# wigler_ariel.net
KiCad netlist of a schematic drawn in EasyEDA
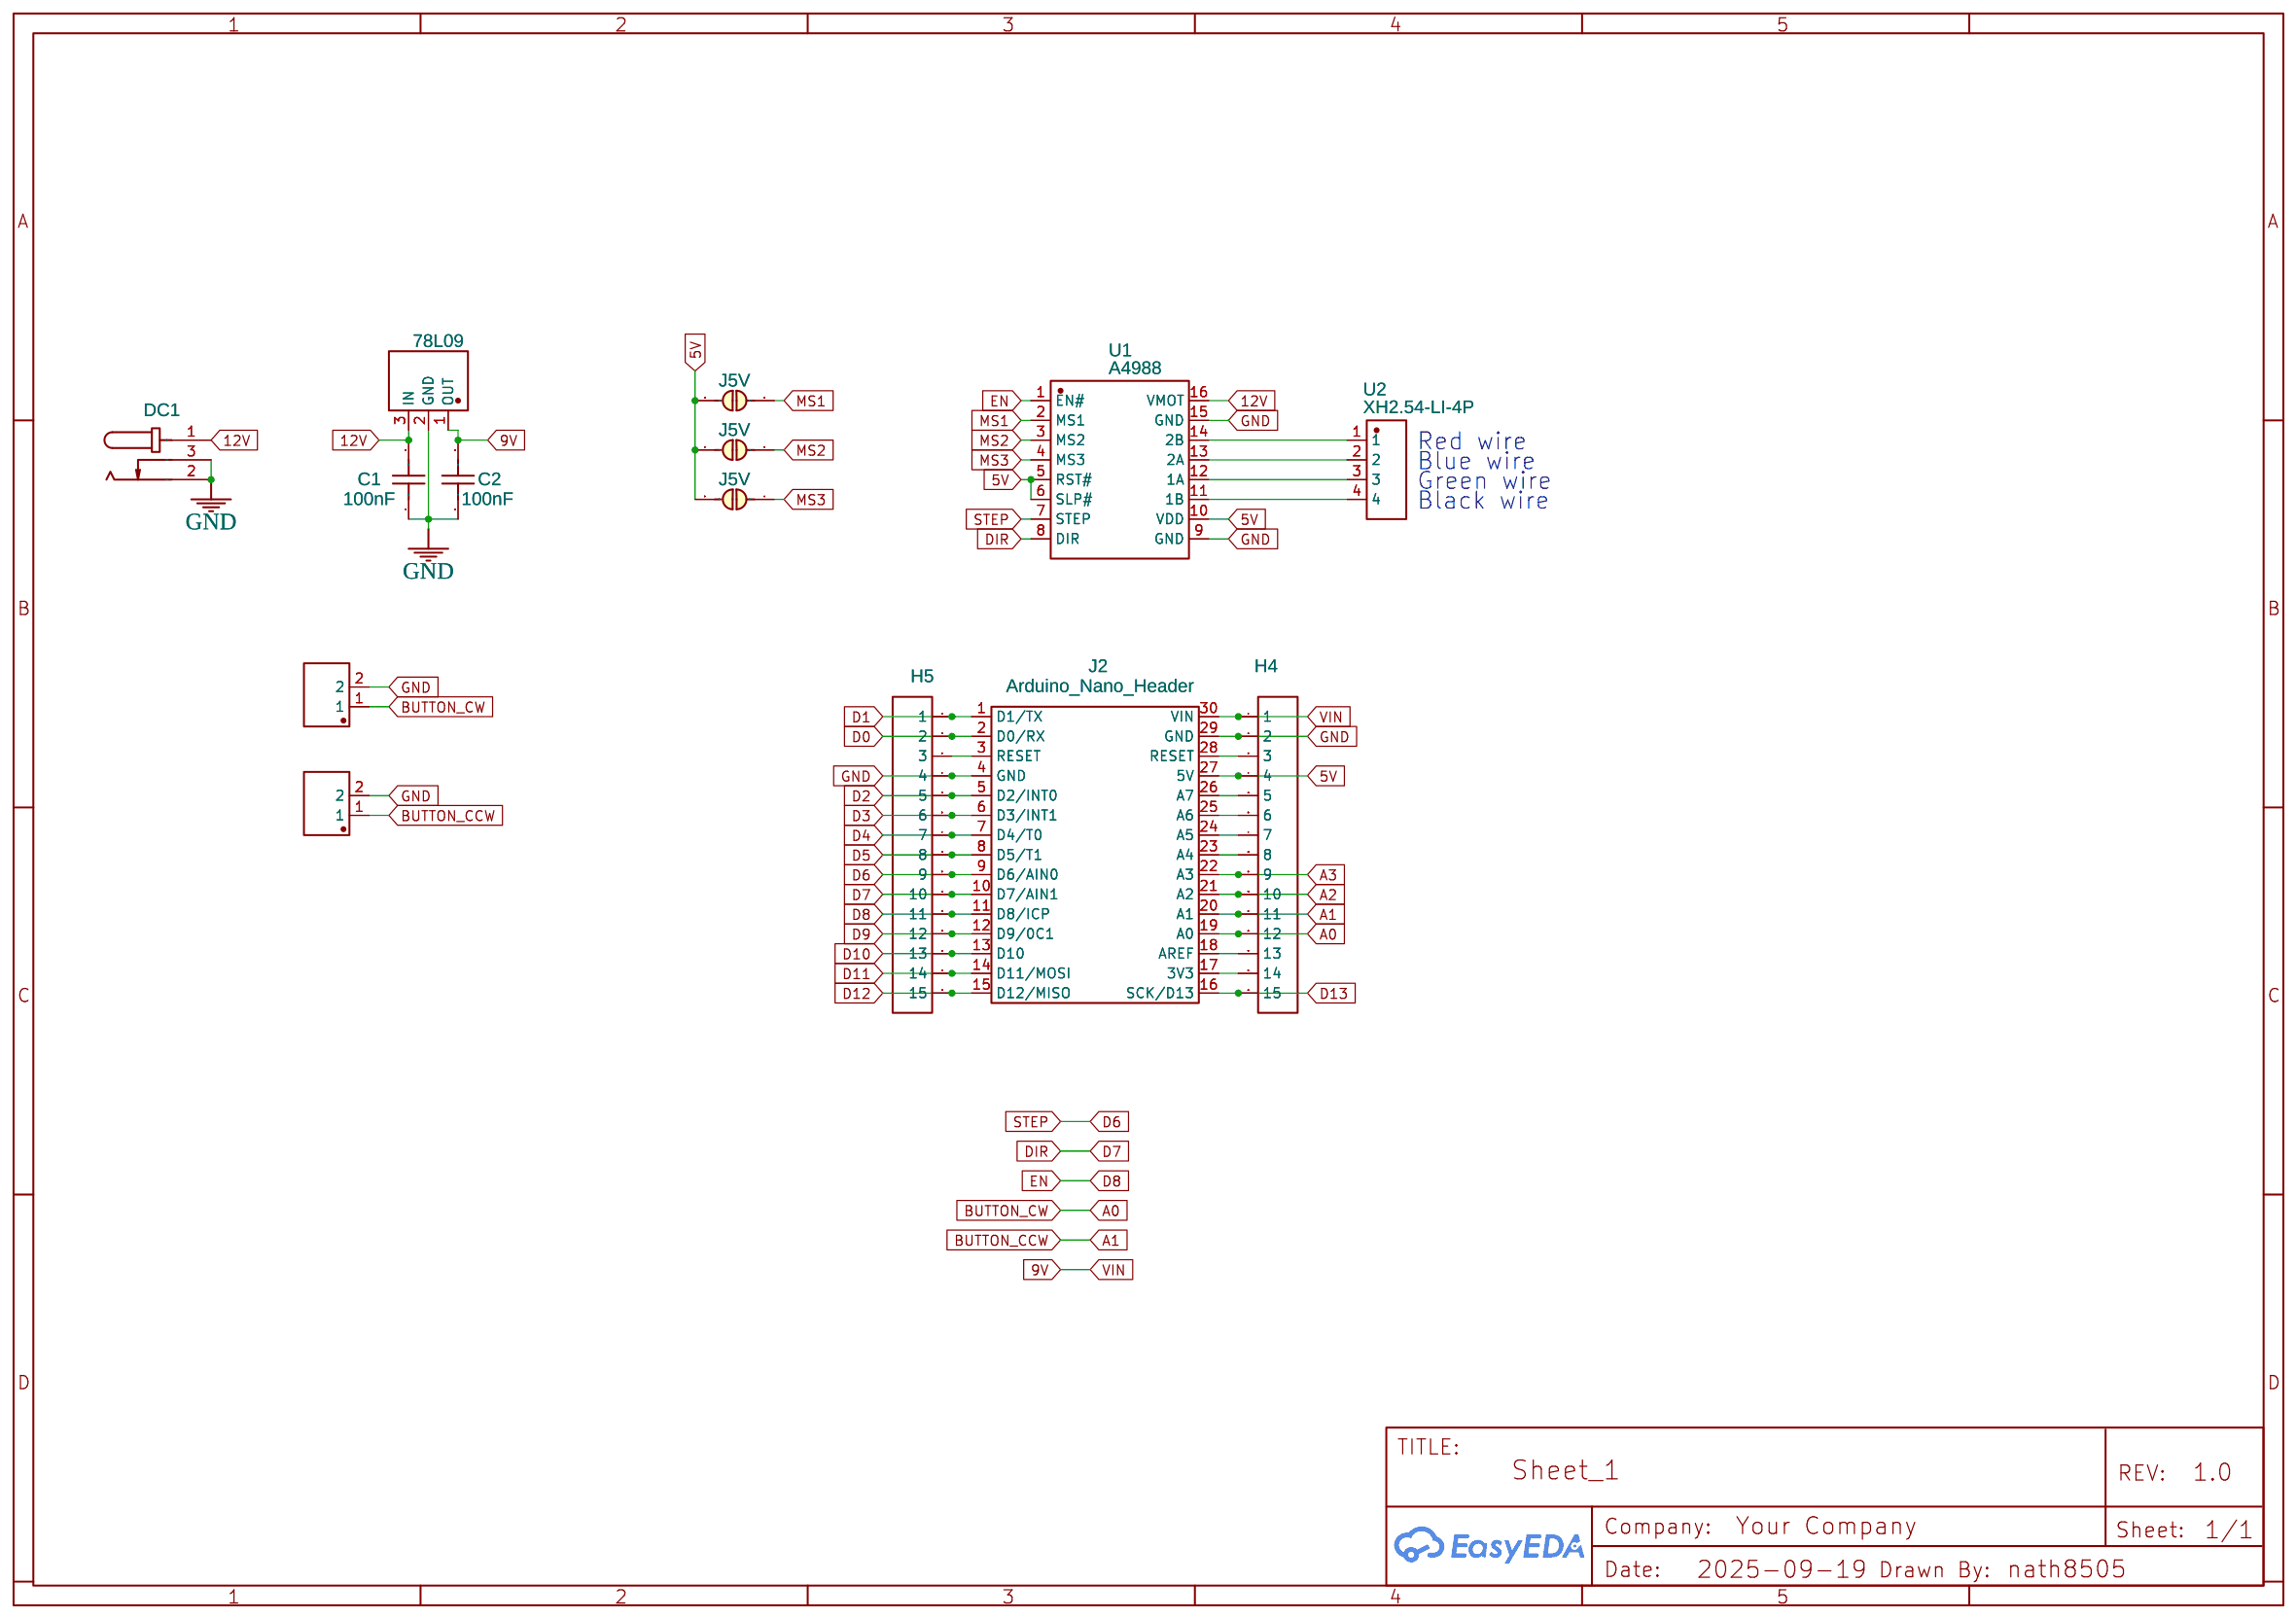
[diagram p0: schematic sheet]

(export (version "E")
  (design (tool "Eeschema 10.0.6"))
  (components
    (comp (ref "C1")
      (value "100nF")
      (fields
        (field (name "Manufacturer Part") "CC0603KRX7R9BB104")
        (field (name "Manufacturer") "YAGEO(国巨)")
      )
      (libsource (lib "") (part "CC0603KRX7R9BB104"))
    )
    (comp (ref "C2")
      (value "100nF")
      (fields
        (field (name "Manufacturer Part") "CC0603KRX7R9BB104")
        (field (name "Manufacturer") "YAGEO(国巨)")
      )
      (libsource (lib "") (part "CC0603KRX7R9BB104"))
    )
    (comp (ref "D7")
      (value "B+")
      (fields (field (name "Manufacturer Part") "KF2510-2A") (field (name "Manufacturer") "BOOMELE"))
      (libsource (lib "") (part "KF2510-2A"))
    )
    (comp (ref "D8")
      (value "B-")
      (fields (field (name "Manufacturer Part") "KF2510-2A") (field (name "Manufacturer") "BOOMELE"))
      (libsource (lib "") (part "KF2510-2A"))
    )
    (comp (ref "DC1")
      (value "DC")
      (fields (field (name "Manufacturer Part") "DC005-2.0MM") (field (name "Manufacturer") "SOFNG"))
      (libsource (lib "") (part "DC005-2.0MM"))
    )
    (comp (ref "H4") (value "HDR-F-2.54_1x15") (libsource (lib "") (part "HDR-F-2.54_1x15")))
    (comp (ref "H5") (value "HDR-F-2.54_1x15") (libsource (lib "") (part "HDR-F-2.54_1x15_1")))
    (comp (ref "J2") (value "Arduino_Nano_Header") (libsource (lib "") (part "Arduino_Nano_Header")))
    (comp (ref "J9V_1") (value "J5V") (libsource (lib "") (part "JUMPER-SMT_2")))
    (comp (ref "J9V_2") (value "J5V") (libsource (lib "") (part "JUMPER-SMT_2")))
    (comp (ref "J9V_3") (value "J5V") (libsource (lib "") (part "JUMPER-SMT_2")))
    (comp (ref "U1") (value "A4988") (libsource (lib "") (part "A4988")))
    (comp (ref "U2") (value "XH2.54-LI-4P") (libsource (lib "") (part "XH2.54-LI-4P")))
    (comp (ref "U3")
      (value "78L09")
      (fields (field (name "Manufacturer") "CBI(创基)"))
      (libsource (lib "") (part "78L09U 78L09"))
    )
  )
  (nets
    (net (code "1") (name "5V") (class "Default")
      (node (ref "H4") (pin "4") (pinfunction "4_4") (pintype "unspecified"))
      (node (ref "J2") (pin "27") (pinfunction "5V_27") (pintype "unspecified"))
      (node (ref "J9V_1") (pin "2") (pinfunction "2_2") (pintype "bidirectional"))
      (node (ref "J9V_2") (pin "2") (pinfunction "2_2") (pintype "bidirectional"))
      (node (ref "J9V_3") (pin "2") (pinfunction "2_2") (pintype "bidirectional"))
      (node (ref "U1") (pin "10") (pinfunction "VDD_10") (pintype "unspecified"))
      (node (ref "U1") (pin "5") (pinfunction "RST#_5") (pintype "unspecified"))
      (node (ref "U1") (pin "6") (pinfunction "SLP#_6") (pintype "unspecified"))
    )
    (net (code "2") (name "9V") (class "Default")
      (node (ref "C2") (pin "2") (pinfunction "2_2") (pintype "unspecified"))
      (node (ref "H4") (pin "1") (pinfunction "1_1") (pintype "unspecified"))
      (node (ref "J2") (pin "30") (pinfunction "VIN_30") (pintype "unspecified"))
      (node (ref "U3") (pin "1") (pinfunction "OUT_1") (pintype "unspecified"))
    )
    (net (code "3") (name "12V") (class "Default")
      (node (ref "C1") (pin "2") (pinfunction "2_2") (pintype "unspecified"))
      (node (ref "DC1") (pin "1") (pinfunction "1_1") (pintype "unspecified"))
      (node (ref "U1") (pin "16") (pinfunction "VMOT_16") (pintype "unspecified"))
      (node (ref "U3") (pin "3") (pinfunction "IN_3") (pintype "unspecified"))
    )
    (net (code "4") (name "A0") (class "Default")
      (node (ref "D7") (pin "1") (pinfunction "1_1") (pintype "unspecified"))
      (node (ref "H4") (pin "12") (pinfunction "12_12") (pintype "unspecified"))
      (node (ref "J2") (pin "19") (pinfunction "A0_19") (pintype "unspecified"))
    )
    (net (code "5") (name "A1") (class "Default")
      (node (ref "D8") (pin "1") (pinfunction "1_1") (pintype "unspecified"))
      (node (ref "H4") (pin "11") (pinfunction "11_11") (pintype "unspecified"))
      (node (ref "J2") (pin "20") (pinfunction "A1_20") (pintype "unspecified"))
    )
    (net (code "6") (name "A2") (class "Default")
      (node (ref "H4") (pin "10") (pinfunction "10_10") (pintype "unspecified"))
      (node (ref "J2") (pin "21") (pinfunction "A2_21") (pintype "unspecified"))
    )
    (net (code "7") (name "A3") (class "Default")
      (node (ref "H4") (pin "9") (pinfunction "9_9") (pintype "unspecified"))
      (node (ref "J2") (pin "22") (pinfunction "A3_22") (pintype "unspecified"))
    )
    (net (code "8") (name "D0") (class "Default")
      (node (ref "H5") (pin "2") (pinfunction "2_2") (pintype "unspecified"))
      (node (ref "J2") (pin "2") (pinfunction "D0/RX_2") (pintype "unspecified"))
    )
    (net (code "9") (name "D1") (class "Default")
      (node (ref "H5") (pin "1") (pinfunction "1_1") (pintype "unspecified"))
      (node (ref "J2") (pin "1") (pinfunction "D1/TX_1") (pintype "unspecified"))
    )
    (net (code "10") (name "D2") (class "Default")
      (node (ref "H5") (pin "5") (pinfunction "5_5") (pintype "unspecified"))
      (node (ref "J2") (pin "5") (pinfunction "D2/INT0_5") (pintype "unspecified"))
    )
    (net (code "11") (name "D3") (class "Default")
      (node (ref "H5") (pin "6") (pinfunction "6_6") (pintype "unspecified"))
      (node (ref "J2") (pin "6") (pinfunction "D3/INT1_6") (pintype "unspecified"))
    )
    (net (code "12") (name "D4") (class "Default")
      (node (ref "H5") (pin "7") (pinfunction "7_7") (pintype "unspecified"))
      (node (ref "J2") (pin "7") (pinfunction "D4/T0_7") (pintype "unspecified"))
    )
    (net (code "13") (name "D5") (class "Default")
      (node (ref "H5") (pin "8") (pinfunction "8_8") (pintype "unspecified"))
      (node (ref "J2") (pin "8") (pinfunction "D5/T1_8") (pintype "unspecified"))
    )
    (net (code "14") (name "D6") (class "Default")
      (node (ref "H5") (pin "9") (pinfunction "9_9") (pintype "unspecified"))
      (node (ref "J2") (pin "9") (pinfunction "D6/AIN0_9") (pintype "unspecified"))
      (node (ref "U1") (pin "7") (pinfunction "STEP_7") (pintype "unspecified"))
    )
    (net (code "15") (name "D7") (class "Default")
      (node (ref "H5") (pin "10") (pinfunction "10_10") (pintype "unspecified"))
      (node (ref "J2") (pin "10") (pinfunction "D7/AIN1_10") (pintype "unspecified"))
      (node (ref "U1") (pin "8") (pinfunction "DIR_8") (pintype "unspecified"))
    )
    (net (code "16") (name "D8") (class "Default")
      (node (ref "H5") (pin "11") (pinfunction "11_11") (pintype "unspecified"))
      (node (ref "J2") (pin "11") (pinfunction "D8/ICP_11") (pintype "unspecified"))
      (node (ref "U1") (pin "1") (pinfunction "EN#_1") (pintype "unspecified"))
    )
    (net (code "17") (name "D9") (class "Default")
      (node (ref "H5") (pin "12") (pinfunction "12_12") (pintype "unspecified"))
      (node (ref "J2") (pin "12") (pinfunction "D9/0C1_12") (pintype "unspecified"))
    )
    (net (code "18") (name "D10") (class "Default")
      (node (ref "H5") (pin "13") (pinfunction "13_13") (pintype "unspecified"))
      (node (ref "J2") (pin "13") (pinfunction "D10_13") (pintype "unspecified"))
    )
    (net (code "19") (name "D11") (class "Default")
      (node (ref "H5") (pin "14") (pinfunction "14_14") (pintype "unspecified"))
      (node (ref "J2") (pin "14") (pinfunction "D11/MOSI_14") (pintype "unspecified"))
    )
    (net (code "20") (name "D12") (class "Default")
      (node (ref "H5") (pin "15") (pinfunction "15_15") (pintype "unspecified"))
      (node (ref "J2") (pin "15") (pinfunction "D12/MISO_15") (pintype "unspecified"))
    )
    (net (code "21") (name "D13") (class "Default")
      (node (ref "H4") (pin "15") (pinfunction "15_15") (pintype "unspecified"))
      (node (ref "J2") (pin "16") (pinfunction "SCK/D13_16") (pintype "unspecified"))
    )
    (net (code "22") (name "GND") (class "Default")
      (node (ref "C1") (pin "1") (pinfunction "1_1") (pintype "unspecified"))
      (node (ref "C2") (pin "1") (pinfunction "1_1") (pintype "unspecified"))
      (node (ref "D7") (pin "2") (pinfunction "2_2") (pintype "unspecified"))
      (node (ref "D8") (pin "2") (pinfunction "2_2") (pintype "unspecified"))
      (node (ref "DC1") (pin "2") (pinfunction "2_2") (pintype "unspecified"))
      (node (ref "DC1") (pin "3") (pinfunction "3_3") (pintype "unspecified"))
      (node (ref "H4") (pin "2") (pinfunction "2_2") (pintype "unspecified"))
      (node (ref "H5") (pin "4") (pinfunction "4_4") (pintype "unspecified"))
      (node (ref "J2") (pin "29") (pinfunction "GND_29") (pintype "unspecified"))
      (node (ref "J2") (pin "4") (pinfunction "GND_4") (pintype "unspecified"))
      (node (ref "U1") (pin "15") (pinfunction "GND_15") (pintype "unspecified"))
      (node (ref "U1") (pin "9") (pinfunction "GND_9") (pintype "unspecified"))
      (node (ref "U3") (pin "2") (pinfunction "GND_2") (pintype "unspecified"))
    )
    (net (code "23") (name "MS1") (class "Default")
      (node (ref "J9V_1") (pin "1") (pinfunction "1_1") (pintype "bidirectional"))
      (node (ref "U1") (pin "2") (pinfunction "MS1_2") (pintype "unspecified"))
    )
    (net (code "24") (name "MS2") (class "Default")
      (node (ref "J9V_2") (pin "1") (pinfunction "1_1") (pintype "bidirectional"))
      (node (ref "U1") (pin "3") (pinfunction "MS2_3") (pintype "unspecified"))
    )
    (net (code "25") (name "MS3") (class "Default")
      (node (ref "J9V_3") (pin "1") (pinfunction "1_1") (pintype "bidirectional"))
      (node (ref "U1") (pin "4") (pinfunction "MS3_4") (pintype "unspecified"))
    )
    (net (code "26") (name "Net-(H4-Pad3)") (class "Default")
      (node (ref "H4") (pin "3") (pinfunction "3_3") (pintype "unspecified"))
      (node (ref "J2") (pin "28") (pinfunction "RESET_28") (pintype "unspecified"))
    )
    (net (code "27") (name "Net-(H5-Pad3)") (class "Default")
      (node (ref "H5") (pin "3") (pinfunction "3_3") (pintype "unspecified"))
      (node (ref "J2") (pin "3") (pinfunction "RESET_3") (pintype "unspecified"))
    )
    (net (code "28") (name "Net-(J2-3V3)") (class "Default")
      (node (ref "H4") (pin "14") (pinfunction "14_14") (pintype "unspecified"))
      (node (ref "J2") (pin "17") (pinfunction "3V3_17") (pintype "unspecified"))
    )
    (net (code "29") (name "Net-(J2-A4)") (class "Default")
      (node (ref "H4") (pin "8") (pinfunction "8_8") (pintype "unspecified"))
      (node (ref "J2") (pin "23") (pinfunction "A4_23") (pintype "unspecified"))
    )
    (net (code "30") (name "Net-(J2-A5)") (class "Default")
      (node (ref "H4") (pin "7") (pinfunction "7_7") (pintype "unspecified"))
      (node (ref "J2") (pin "24") (pinfunction "A5_24") (pintype "unspecified"))
    )
    (net (code "31") (name "Net-(J2-A6)") (class "Default")
      (node (ref "H4") (pin "6") (pinfunction "6_6") (pintype "unspecified"))
      (node (ref "J2") (pin "25") (pinfunction "A6_25") (pintype "unspecified"))
    )
    (net (code "32") (name "Net-(J2-A7)") (class "Default")
      (node (ref "H4") (pin "5") (pinfunction "5_5") (pintype "unspecified"))
      (node (ref "J2") (pin "26") (pinfunction "A7_26") (pintype "unspecified"))
    )
    (net (code "33") (name "Net-(J2-AREF)") (class "Default")
      (node (ref "H4") (pin "13") (pinfunction "13_13") (pintype "unspecified"))
      (node (ref "J2") (pin "18") (pinfunction "AREF_18") (pintype "unspecified"))
    )
    (net (code "34") (name "Net-(U1-1A)") (class "Default")
      (node (ref "U1") (pin "12") (pinfunction "1A_12") (pintype "unspecified"))
      (node (ref "U2") (pin "3") (pinfunction "3_3") (pintype "unspecified"))
    )
    (net (code "35") (name "Net-(U1-1B)") (class "Default")
      (node (ref "U1") (pin "11") (pinfunction "1B_11") (pintype "unspecified"))
      (node (ref "U2") (pin "4") (pinfunction "4_4") (pintype "unspecified"))
    )
    (net (code "36") (name "Net-(U1-2A)") (class "Default")
      (node (ref "U1") (pin "13") (pinfunction "2A_13") (pintype "unspecified"))
      (node (ref "U2") (pin "2") (pinfunction "2_2") (pintype "unspecified"))
    )
    (net (code "37") (name "Net-(U1-2B)") (class "Default")
      (node (ref "U1") (pin "14") (pinfunction "2B_14") (pintype "unspecified"))
      (node (ref "U2") (pin "1") (pinfunction "1_1") (pintype "unspecified"))
    )
  )
)
